# Power.net
KiCad netlist of a schematic drawn in Altium Designer
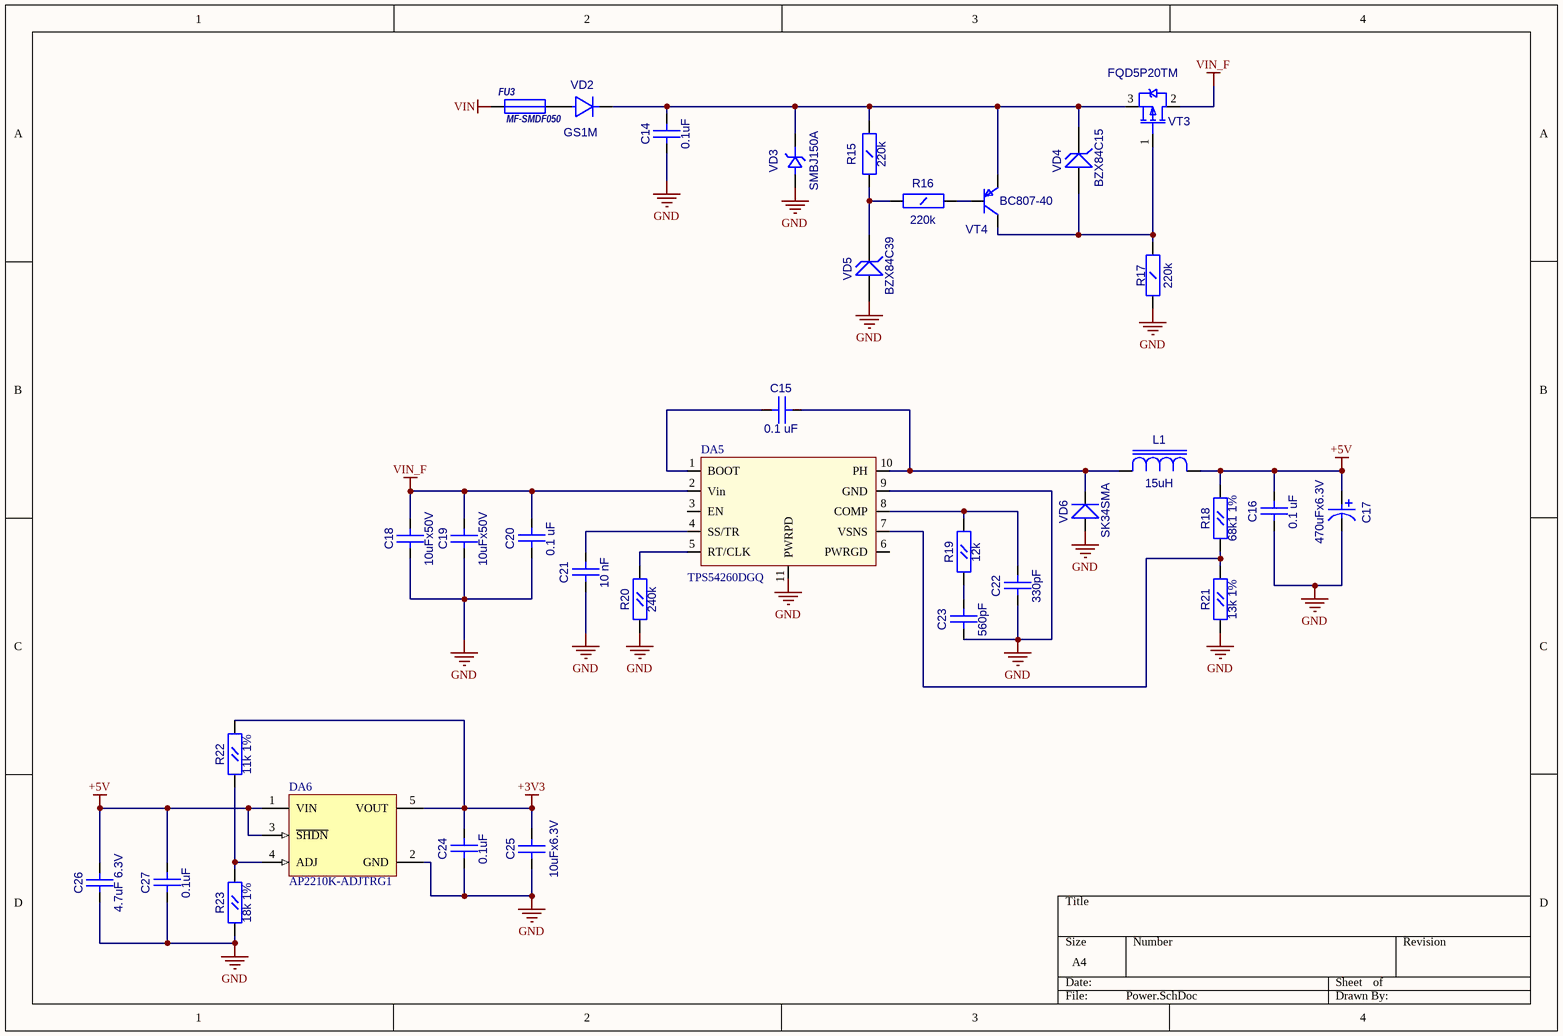
[diagram p0: Power.SchDoc]

(export (version "E")
  (design (tool "Eeschema 10.0.6"))
  (components
    (comp (ref "C14")
      (value "0.1uF")
      (footprint "CC1206")
      (description "CC1206")
      (libsource (lib "gprs_modem_2") (part "CC1206"))
    )
    (comp (ref "C15")
      (value "0.1 uF")
      (footprint "CC0603")
      (description "CC0603")
      (libsource (lib "gprs_modem_2") (part "CC0603"))
    )
    (comp (ref "C16")
      (value "0.1 uF")
      (footprint "CC0603")
      (description "CC0603")
      (libsource (lib "gprs_modem_2") (part "CC0603"))
    )
    (comp (ref "C17")
      (value "470uFx6.3V")
      (footprint "TAJ-D-1M")
      (description "TAJ-D")
      (libsource (lib "gprs_modem_2") (part "TAJ-D"))
    )
    (comp (ref "C18")
      (value "10uFx50V")
      (footprint "CC1210")
      (description "CC1210")
      (libsource (lib "gprs_modem_2") (part "CC1210"))
    )
    (comp (ref "C19")
      (value "10uFx50V")
      (footprint "CC1210")
      (description "CC1210")
      (libsource (lib "gprs_modem_2") (part "CC1210"))
    )
    (comp (ref "C20")
      (value "0.1 uF")
      (footprint "CC0603")
      (description "CC0603")
      (libsource (lib "gprs_modem_2") (part "CC0603"))
    )
    (comp (ref "C21")
      (value "10 nF")
      (footprint "CC0603")
      (description "CC0603")
      (libsource (lib "gprs_modem_2") (part "CC0603"))
    )
    (comp (ref "C22")
      (value "330pF")
      (footprint "CC0603")
      (description "CC0603")
      (libsource (lib "gprs_modem_2") (part "CC0603"))
    )
    (comp (ref "C23")
      (value "560pF")
      (footprint "CC0603")
      (description "CC0603")
      (libsource (lib "gprs_modem_2") (part "CC0603"))
    )
    (comp (ref "C24")
      (value "0.1uF")
      (footprint "CC0603")
      (description "CC0603")
      (libsource (lib "gprs_modem_2") (part "CC0603"))
    )
    (comp (ref "C25")
      (value "10uFx6.3V")
      (footprint "CC0805")
      (description "CC0805")
      (libsource (lib "gprs_modem_2") (part "CC0805"))
    )
    (comp (ref "C26")
      (value "4.7uF 6.3V")
      (footprint "CC0805")
      (description "CC0805")
      (libsource (lib "gprs_modem_2") (part "CC0805"))
    )
    (comp (ref "C27")
      (value "0.1uF")
      (footprint "CC0603")
      (description "CC0603")
      (libsource (lib "gprs_modem_2") (part "CC0603"))
    )
    (comp (ref "DA5")
      (value "TPS54260DGQ")
      (footprint "S-PDSO-G10")
      (libsource (lib "gprs_modem") (part "TPS54260DGQ"))
    )
    (comp (ref "DA6")
      (value "AP2210K-ADJTRG1")
      (footprint "SOT23-5")
      (fields (field (name "PUBLISHER") "Altium Limited"))
      (libsource (lib "gprs_modem_2") (part "MCP1824T-ADJE/OT"))
    )
    (comp (ref "FU3")
      (value "MF-SMDF050")
      (footprint "MF-SMDF")
      (description "MF-SMDF")
      (libsource (lib "gprs_modem_2") (part "MF-SMDF"))
    )
    (comp (ref "L1")
      (value "15uH")
      (footprint "SDR0603")
      (description "SDR0603")
      (libsource (lib "gprs_modem_2") (part "SDR0603"))
    )
    (comp (ref "R15")
      (value "220k")
      (footprint "RC1206")
      (description "RC1206")
      (libsource (lib "gprs_modem_2") (part "RC1206"))
    )
    (comp (ref "R16")
      (value "220k")
      (footprint "RC1206")
      (description "RC1206")
      (libsource (lib "gprs_modem_2") (part "RC1206"))
    )
    (comp (ref "R17")
      (value "220k")
      (footprint "RC1206")
      (description "RC1206")
      (libsource (lib "gprs_modem_2") (part "RC1206"))
    )
    (comp (ref "R18")
      (value "68k1 1%")
      (footprint "RC0603")
      (description "RC0603")
      (libsource (lib "gprs_modem_2") (part "RC0603"))
    )
    (comp (ref "R19")
      (value "12k")
      (footprint "RC0603")
      (description "RC0603")
      (libsource (lib "gprs_modem_2") (part "RC0603"))
    )
    (comp (ref "R20")
      (value "240k")
      (footprint "RC0603")
      (description "RC0603")
      (libsource (lib "gprs_modem_2") (part "RC0603"))
    )
    (comp (ref "R21")
      (value "13k 1%")
      (footprint "RC0603")
      (description "RC0603")
      (libsource (lib "gprs_modem_2") (part "RC0603"))
    )
    (comp (ref "R22")
      (value "11k 1%")
      (footprint "RC0603")
      (description "RC0603")
      (libsource (lib "gprs_modem_2") (part "RC0603"))
    )
    (comp (ref "R23")
      (value "18k 1%")
      (footprint "RC0603")
      (description "RC0603")
      (libsource (lib "gprs_modem_2") (part "RC0603"))
    )
    (comp (ref "VD2") (value "GS1M") (footprint "SMA") (libsource (lib "gprs_modem") (part "GS1M")))
    (comp (ref "VD3")
      (value "SMBJ150A")
      (footprint "SMB")
      (description "SMBJ")
      (libsource (lib "gprs_modem_2") (part "SMBJ"))
    )
    (comp (ref "VD4")
      (value "BZX84C15")
      (footprint "SOT-23(123)")
      (description "Zener Voltage Regulator Diode")
      (libsource (lib "gprs_modem_2") (part "BZX84"))
    )
    (comp (ref "VD5")
      (value "BZX84C39")
      (footprint "SOT-23(123)")
      (description "Zener Voltage Regulator Diode")
      (libsource (lib "gprs_modem_2") (part "BZX84"))
    )
    (comp (ref "VD6")
      (value "SK34SMA")
      (footprint "SMA")
      (description "Schottky Rectifier")
      (libsource (lib "gprs_modem") (part "SK34SMA"))
    )
    (comp (ref "VT3")
      (value "FQD5P20TM")
      (footprint "D-PAK(TO-252AA)")
      (description "HEXFET Power MOSFET")
      (libsource (lib "gprs_modem_2") (part "IRFR9220"))
    )
    (comp (ref "VT4")
      (value "BC807-40")
      (footprint "SOT-23(123)")
      (description "BC857B")
      (libsource (lib "gprs_modem") (part "BC857B"))
    )
  )
  (nets
    (net (code "1") (name "+3V3") (class "Default")
      (node (ref "C24") (pin "1") (pinfunction "A_1") (pintype "passive"))
      (node (ref "C25") (pin "2") (pinfunction "B_2") (pintype "passive"))
      (node (ref "DA6") (pin "5") (pinfunction "VOUT_5") (pintype "power_in"))
      (node (ref "R22") (pin "2") (pinfunction "B_2") (pintype "passive"))
    )
    (net (code "2") (name "+5V") (class "Default")
      (node (ref "C16") (pin "1") (pinfunction "A_1") (pintype "passive"))
      (node (ref "C17") (pin "1") (pinfunction "A_1") (pintype "passive"))
      (node (ref "C26") (pin "2") (pinfunction "B_2") (pintype "passive"))
      (node (ref "C27") (pin "1") (pinfunction "A_1") (pintype "passive"))
      (node (ref "DA6") (pin "1") (pinfunction "VIN_1") (pintype "power_in"))
      (node (ref "DA6") (pin "3") (pinfunction "~{SHDN}_3") (pintype "input"))
      (node (ref "L1") (pin "2") (pintype "passive"))
      (node (ref "R18") (pin "2") (pinfunction "B_2") (pintype "passive"))
    )
    (net (code "3") (name "GND") (class "Default")
      (node (ref "C14") (pin "1") (pinfunction "A_1") (pintype "passive"))
      (node (ref "C16") (pin "2") (pinfunction "B_2") (pintype "passive"))
      (node (ref "C17") (pin "2") (pinfunction "B_2") (pintype "passive"))
      (node (ref "C18") (pin "1") (pinfunction "A_1") (pintype "passive"))
      (node (ref "C19") (pin "1") (pinfunction "A_1") (pintype "passive"))
      (node (ref "C20") (pin "2") (pinfunction "B_2") (pintype "passive"))
      (node (ref "C21") (pin "2") (pinfunction "B_2") (pintype "passive"))
      (node (ref "C22") (pin "2") (pinfunction "B_2") (pintype "passive"))
      (node (ref "C23") (pin "2") (pinfunction "B_2") (pintype "passive"))
      (node (ref "C24") (pin "2") (pinfunction "B_2") (pintype "passive"))
      (node (ref "C25") (pin "1") (pinfunction "A_1") (pintype "passive"))
      (node (ref "C26") (pin "1") (pinfunction "A_1") (pintype "passive"))
      (node (ref "C27") (pin "2") (pinfunction "B_2") (pintype "passive"))
      (node (ref "DA5") (pin "11") (pinfunction "PWRPD_11") (pintype "passive"))
      (node (ref "DA5") (pin "9") (pinfunction "GND_9") (pintype "passive"))
      (node (ref "DA6") (pin "2") (pinfunction "GND_2") (pintype "power_in"))
      (node (ref "R17") (pin "2") (pinfunction "B_2") (pintype "passive"))
      (node (ref "R20") (pin "1") (pinfunction "A_1") (pintype "passive"))
      (node (ref "R21") (pin "1") (pinfunction "A_1") (pintype "passive"))
      (node (ref "R23") (pin "1") (pinfunction "A_1") (pintype "passive"))
      (node (ref "VD3") (pin "1") (pinfunction "A_1") (pintype "passive"))
      (node (ref "VD5") (pin "1") (pinfunction "A_1") (pintype "passive"))
      (node (ref "VD6") (pin "1") (pinfunction "A_1") (pintype "passive"))
    )
    (net (code "4") (name "Net-(C14-B)") (class "Default")
      (node (ref "C14") (pin "2") (pinfunction "B_2") (pintype "passive"))
      (node (ref "R15") (pin "2") (pinfunction "B_2") (pintype "passive"))
      (node (ref "VD2") (pin "2") (pinfunction "K_2") (pintype "passive"))
      (node (ref "VD3") (pin "2") (pinfunction "K_2") (pintype "passive"))
      (node (ref "VD4") (pin "3") (pinfunction "K_3") (pintype "passive"))
      (node (ref "VT3") (pin "3") (pinfunction "S_3") (pintype "passive"))
      (node (ref "VT4") (pin "2") (pinfunction "E_2") (pintype "passive"))
    )
    (net (code "5") (name "Net-(C15-A)") (class "Default")
      (node (ref "C15") (pin "1") (pinfunction "A_1") (pintype "passive"))
      (node (ref "DA5") (pin "10") (pinfunction "PH_10") (pintype "passive"))
      (node (ref "L1") (pin "1") (pintype "passive"))
      (node (ref "VD6") (pin "2") (pinfunction "K_2") (pintype "passive"))
    )
    (net (code "6") (name "Net-(C15-B)") (class "Default")
      (node (ref "C15") (pin "2") (pinfunction "B_2") (pintype "passive"))
      (node (ref "DA5") (pin "1") (pinfunction "BOOT_1") (pintype "passive"))
    )
    (net (code "7") (name "Net-(C21-A)") (class "Default")
      (node (ref "C21") (pin "1") (pinfunction "A_1") (pintype "passive"))
      (node (ref "DA5") (pin "4") (pinfunction "SS/TR_4") (pintype "passive"))
    )
    (net (code "8") (name "Net-(C22-A)") (class "Default")
      (node (ref "C22") (pin "1") (pinfunction "A_1") (pintype "passive"))
      (node (ref "DA5") (pin "8") (pinfunction "COMP_8") (pintype "passive"))
      (node (ref "R19") (pin "2") (pinfunction "B_2") (pintype "passive"))
    )
    (net (code "9") (name "Net-(C23-A)") (class "Default")
      (node (ref "C23") (pin "1") (pinfunction "A_1") (pintype "passive"))
      (node (ref "R19") (pin "1") (pinfunction "A_1") (pintype "passive"))
    )
    (net (code "10") (name "Net-(DA5-RT{slash}CLK)") (class "Default")
      (node (ref "DA5") (pin "5") (pinfunction "RT/CLK_5") (pintype "passive"))
      (node (ref "R20") (pin "2") (pinfunction "B_2") (pintype "passive"))
    )
    (net (code "11") (name "Net-(DA5-VSNS)") (class "Default")
      (node (ref "DA5") (pin "7") (pinfunction "VSNS_7") (pintype "passive"))
      (node (ref "R18") (pin "1") (pinfunction "A_1") (pintype "passive"))
      (node (ref "R21") (pin "2") (pinfunction "B_2") (pintype "passive"))
    )
    (net (code "12") (name "Net-(DA6-ADJ)") (class "Default")
      (node (ref "DA6") (pin "4") (pinfunction "ADJ_4") (pintype "input"))
      (node (ref "R22") (pin "1") (pinfunction "A_1") (pintype "passive"))
      (node (ref "R23") (pin "2") (pinfunction "B_2") (pintype "passive"))
    )
    (net (code "13") (name "Net-(R15-A)") (class "Default")
      (node (ref "R15") (pin "1") (pinfunction "A_1") (pintype "passive"))
      (node (ref "R16") (pin "1") (pinfunction "A_1") (pintype "passive"))
      (node (ref "VD5") (pin "3") (pinfunction "K_3") (pintype "passive"))
    )
    (net (code "14") (name "Net-(R16-B)") (class "Default")
      (node (ref "R16") (pin "2") (pinfunction "B_2") (pintype "passive"))
      (node (ref "VT4") (pin "1") (pinfunction "B_1") (pintype "passive"))
    )
    (net (code "15") (name "Net-(R17-A)") (class "Default")
      (node (ref "R17") (pin "1") (pinfunction "A_1") (pintype "passive"))
      (node (ref "VD4") (pin "1") (pinfunction "A_1") (pintype "passive"))
      (node (ref "VT3") (pin "1") (pinfunction "G_1") (pintype "passive"))
      (node (ref "VT4") (pin "3") (pinfunction "C_3") (pintype "passive"))
    )
    (net (code "16") (name "Net-(VD2-A)") (class "Default")
      (node (ref "FU3") (pin "2") (pintype "passive"))
      (node (ref "VD2") (pin "1") (pinfunction "A_1") (pintype "passive"))
    )
    (net (code "17") (name "VIN") (class "Default") (node (ref "FU3") (pin "1") (pintype "passive")))
    (net (code "18") (name "VIN_F") (class "Default")
      (node (ref "C18") (pin "2") (pinfunction "B_2") (pintype "passive"))
      (node (ref "C19") (pin "2") (pinfunction "B_2") (pintype "passive"))
      (node (ref "C20") (pin "1") (pinfunction "A_1") (pintype "passive"))
      (node (ref "DA5") (pin "2") (pinfunction "Vin_2") (pintype "passive"))
      (node (ref "VT3") (pin "2") (pinfunction "D_2") (pintype "passive"))
    )
    (net (code "19") (name "unconnected-(DA5-EN-Pad3)") (class "Default")
      (node (ref "DA5") (pin "3") (pinfunction "EN_3") (pintype "passive"))
    )
    (net (code "20") (name "unconnected-(DA5-PWRGD-Pad6)") (class "Default")
      (node (ref "DA5") (pin "6") (pinfunction "PWRGD_6") (pintype "passive"))
    )
  )
)
